# MicroController.net
KiCad netlist of a schematic drawn in Altium Designer
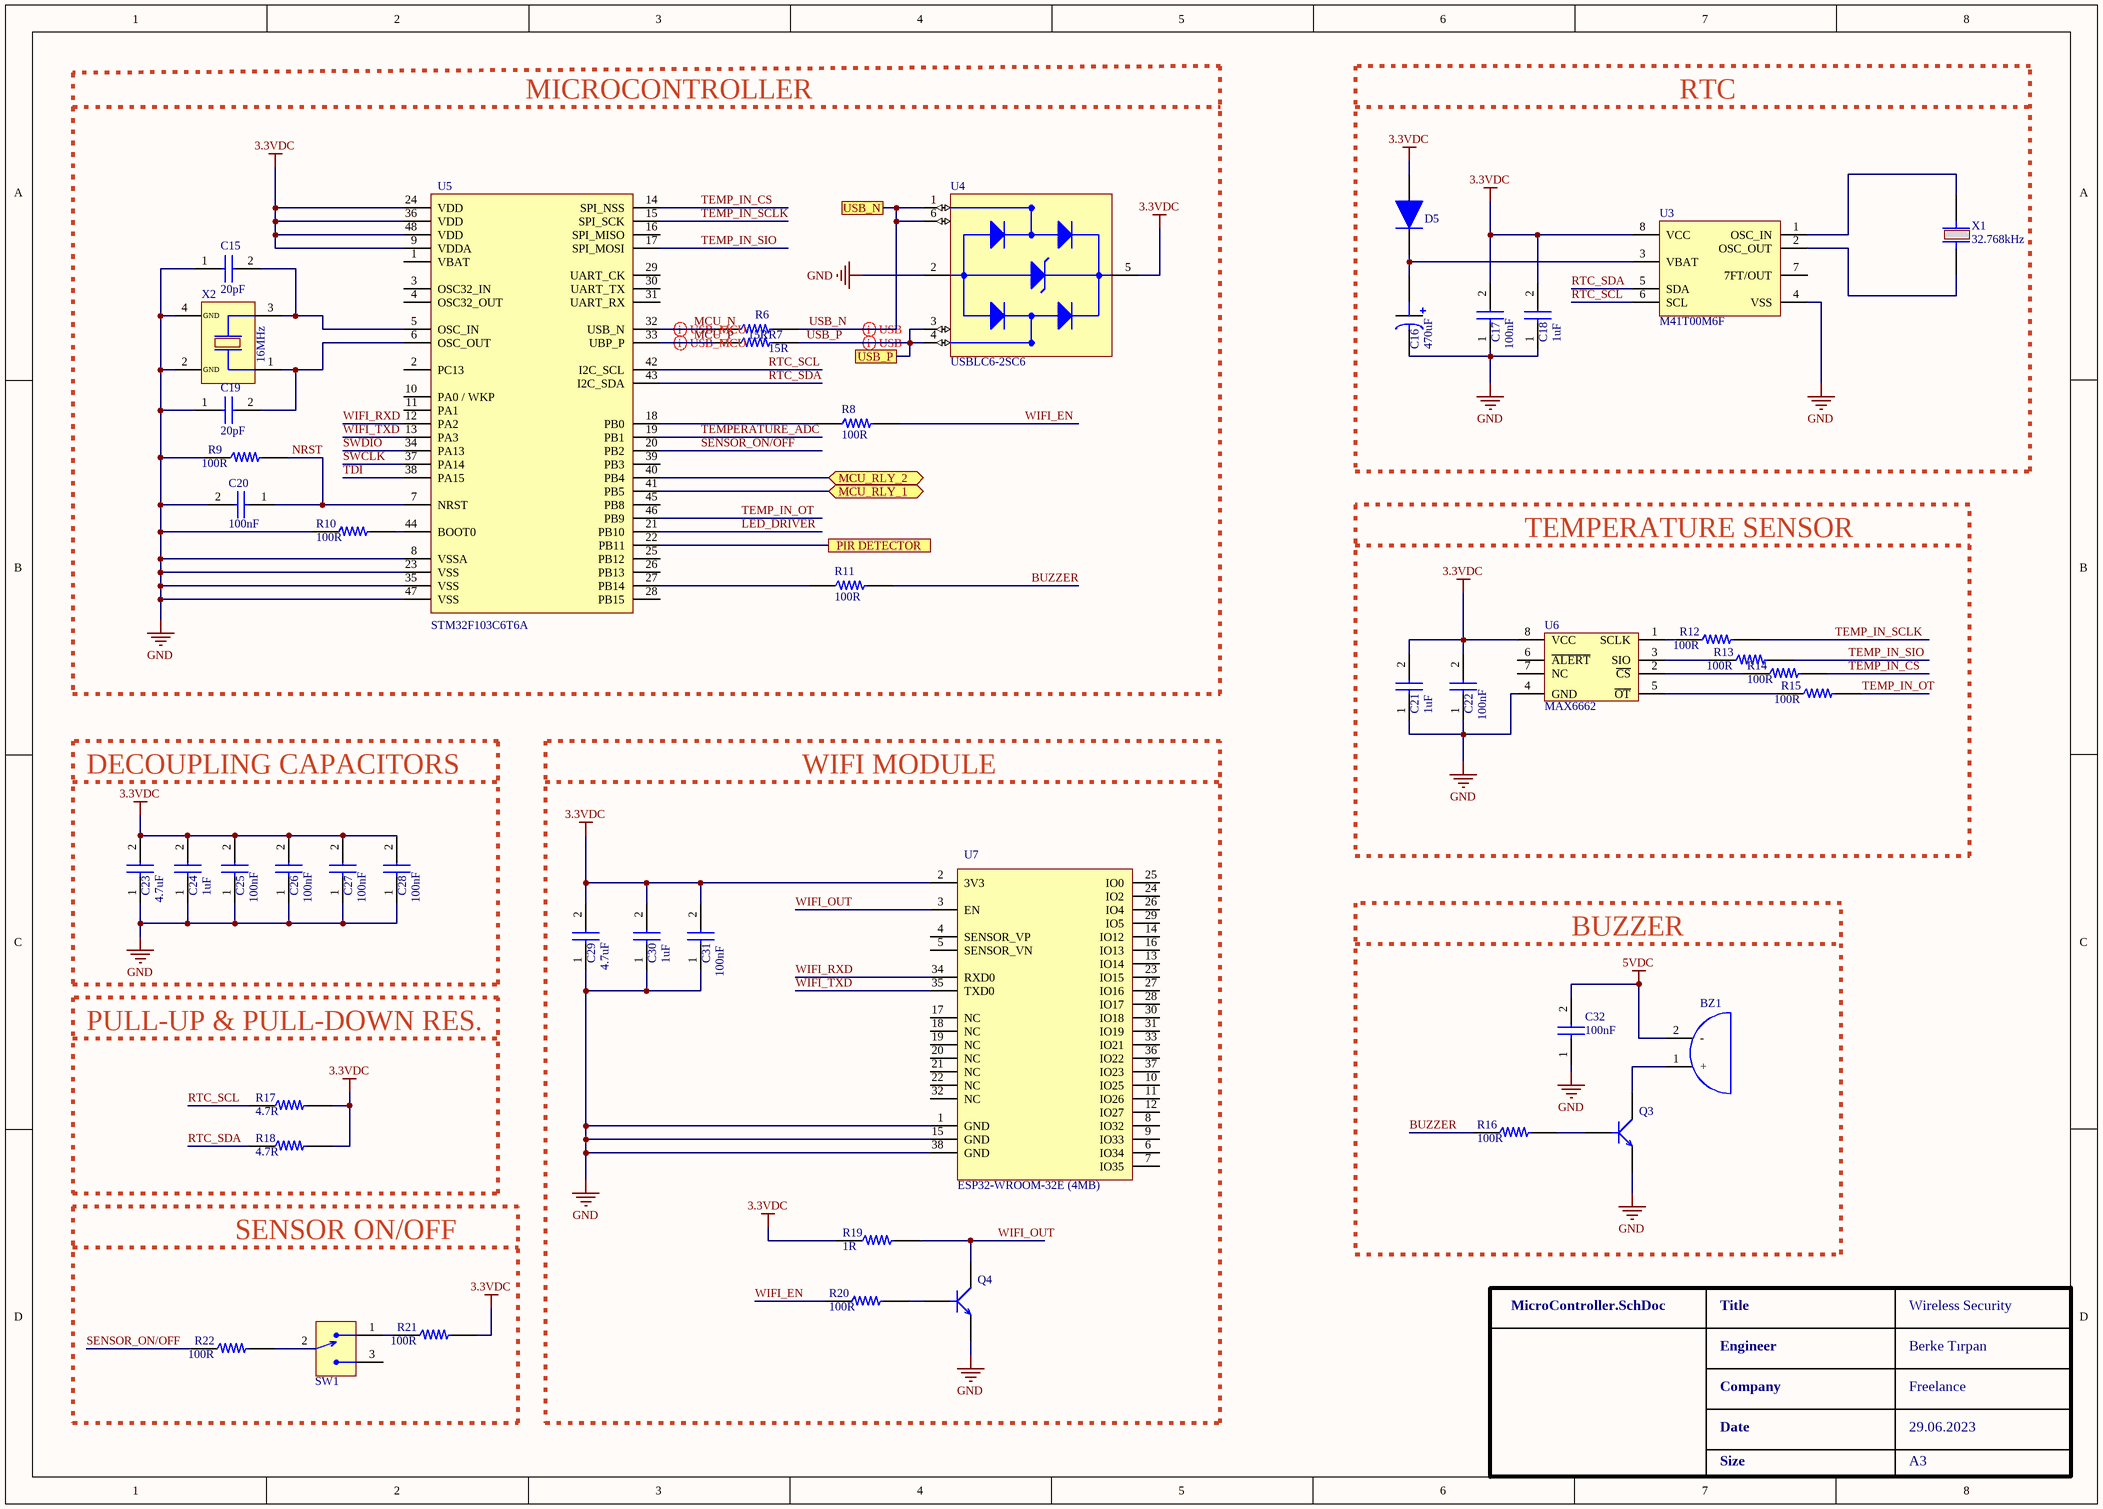
[diagram p0: MicroController.SchDoc]

(export (version "E")
  (design (tool "Eeschema 10.0.6"))
  (components
    (comp (ref "BZ1")
      (value "CMI-9605IC-0580T")
      (footprint "CMI-9605IC-0580T")
      (description "Audio Buzzer Magnetic 3VDC 7VDC 30mA 5VDC 85dB 2600Hz to 2800Hz Through Hole Pin Box")
      (fields (field (name "MANUFACTURER") "CUI Devices"))
      (libsource (lib "Ilk Proje") (part "CMI-9605IC-0580T"))
    )
    (comp (ref "C15")
      (value "CL10C200JB8NNNC")
      (footprint "CAP_0603")
      (description "CAP CER 20PF 50V C0G/NP0 0603")
      (fields
        (field (name "MANUFACTURER") "Samsung")
        (field (name "TOLERANCE") "5%")
        (field (name "CAPACITANCE") "20pF")
      )
      (libsource (lib "Ilk Proje") (part "CAP CER 20pF 0603"))
    )
    (comp (ref "C16")
      (value "ESH477M050AH4AA")
      (footprint "CAP_RADIAL_D10_P5")
      (description "Cap, 470UF, 50V, Alu Elec, Radial")
      (fields
        (field (name "MANUFACTURER") "KEMET")
        (field (name "TOLERANCE") "20%")
        (field (name "CAPACITANCE") "470uF")
      )
      (libsource (lib "Ilk Proje") (part "CAP ALU ELEC 470.UF 50V"))
    )
    (comp (ref "C17")
      (value "CAP CER 100nF 0805")
      (footprint "CAP_0805")
      (description "CAP CER 0.1UF 50V X7R 0805")
      (fields
        (field (name "MANUFACTURER") "Samsung")
        (field (name "MANUFACTURER PART NUMBER") "CL21B104KBCNNNC")
        (field (name "CAPACITANCE") "100nF")
      )
      (libsource (lib "Ilk Proje") (part "CAP CER 100nF 0805"))
    )
    (comp (ref "C18")
      (value "CAP CER 1uF 0805")
      (footprint "CAP_0805")
      (description "CAP CER 1UF 50V X7R %10 0805")
      (fields
        (field (name "MANUFACTURER") "Samsung")
        (field (name "MANUFACTURER PART NUMBER") "CL21B105KBFNNNE")
        (field (name "CAPACITANCE") "1uF")
      )
      (libsource (lib "Ilk Proje") (part "CAP CER 1uF 0805"))
    )
    (comp (ref "C19")
      (value "CL10C200JB8NNNC")
      (footprint "CAP_0603")
      (description "CAP CER 20PF 50V C0G/NP0 0603")
      (fields
        (field (name "MANUFACTURER") "Samsung")
        (field (name "TOLERANCE") "5%")
        (field (name "CAPACITANCE") "20pF")
      )
      (libsource (lib "Ilk Proje") (part "CAP CER 20pF 0603"))
    )
    (comp (ref "C20")
      (value "C0603C104K5RACTU")
      (footprint "CAP_0603")
      (description "Multilayer Ceramic Capacitors (MLCC) - SMD/SMT 50volts 0.1uF X7R 10%")
      (fields
        (field (name "MANUFACTURER") "KEMET")
        (field (name "TOLERANCE") "10%")
        (field (name "CAPACITANCE") "100nF")
      )
      (libsource (lib "Ilk Proje") (part "CAP CER 100nF 0603"))
    )
    (comp (ref "C21")
      (value "CAP CER 1uF 0805")
      (footprint "CAP_0805")
      (description "CAP CER 1UF 50V X7R %10 0805")
      (fields
        (field (name "MANUFACTURER") "Samsung")
        (field (name "MANUFACTURER PART NUMBER") "CL21B105KBFNNNE")
        (field (name "CAPACITANCE") "1uF")
      )
      (libsource (lib "Ilk Proje") (part "CAP CER 1uF 0805"))
    )
    (comp (ref "C22")
      (value "CAP CER 100nF 0805")
      (footprint "CAP_0805")
      (description "CAP CER 0.1UF 50V X7R 0805")
      (fields
        (field (name "MANUFACTURER") "Samsung")
        (field (name "MANUFACTURER PART NUMBER") "CL21B104KBCNNNC")
        (field (name "CAPACITANCE") "100nF")
      )
      (libsource (lib "Ilk Proje") (part "CAP CER 100nF 0805"))
    )
    (comp (ref "C23")
      (value "CAP_CER_4,7UF_0805")
      (footprint "CAP_0805")
      (description "CAP CER 4.7UF 25V %10 0805")
      (fields
        (field (name "MANUFACTURER") "Samsung")
        (field (name "MANUFACTURER PART NUMBER") "CL21A475KAQNNNE")
        (field (name "CAPACITANCE") "4.7uF")
      )
      (libsource (lib "Ilk Proje") (part "CAP_CER_4,7UF_0805"))
    )
    (comp (ref "C24")
      (value "CAP CER 1uF 0805")
      (footprint "CAP_0805")
      (description "CAP CER 1UF 50V X7R %10 0805")
      (fields
        (field (name "MANUFACTURER") "Samsung")
        (field (name "MANUFACTURER PART NUMBER") "CL21B105KBFNNNE")
        (field (name "CAPACITANCE") "1uF")
      )
      (libsource (lib "Ilk Proje") (part "CAP CER 1uF 0805"))
    )
    (comp (ref "C25")
      (value "C0603C104K5RACTU")
      (footprint "CAP_0603")
      (description "Multilayer Ceramic Capacitors (MLCC) - SMD/SMT 50volts 0.1uF X7R 10%")
      (fields
        (field (name "MANUFACTURER") "KEMET")
        (field (name "TOLERANCE") "10%")
        (field (name "CAPACITANCE") "100nF")
      )
      (libsource (lib "Ilk Proje") (part "CAP CER 100nF 0603"))
    )
    (comp (ref "C26")
      (value "C0603C104K5RACTU")
      (footprint "CAP_0603")
      (description "Multilayer Ceramic Capacitors (MLCC) - SMD/SMT 50volts 0.1uF X7R 10%")
      (fields
        (field (name "MANUFACTURER") "KEMET")
        (field (name "TOLERANCE") "10%")
        (field (name "CAPACITANCE") "100nF")
      )
      (libsource (lib "Ilk Proje") (part "CAP CER 100nF 0603"))
    )
    (comp (ref "C27")
      (value "C0603C104K5RACTU")
      (footprint "CAP_0603")
      (description "Multilayer Ceramic Capacitors (MLCC) - SMD/SMT 50volts 0.1uF X7R 10%")
      (fields
        (field (name "MANUFACTURER") "KEMET")
        (field (name "TOLERANCE") "10%")
        (field (name "CAPACITANCE") "100nF")
      )
      (libsource (lib "Ilk Proje") (part "CAP CER 100nF 0603"))
    )
    (comp (ref "C28")
      (value "C0603C104K5RACTU")
      (footprint "CAP_0603")
      (description "Multilayer Ceramic Capacitors (MLCC) - SMD/SMT 50volts 0.1uF X7R 10%")
      (fields
        (field (name "MANUFACTURER") "KEMET")
        (field (name "TOLERANCE") "10%")
        (field (name "CAPACITANCE") "100nF")
      )
      (libsource (lib "Ilk Proje") (part "CAP CER 100nF 0603"))
    )
    (comp (ref "C29")
      (value "CAP_CER_4,7UF_0805")
      (footprint "CAP_0805")
      (description "CAP CER 4.7UF 25V %10 0805")
      (fields
        (field (name "MANUFACTURER") "Samsung")
        (field (name "MANUFACTURER PART NUMBER") "CL21A475KAQNNNE")
        (field (name "CAPACITANCE") "4.7uF")
      )
      (libsource (lib "Ilk Proje") (part "CAP_CER_4,7UF_0805"))
    )
    (comp (ref "C30")
      (value "CAP CER 1uF 0805")
      (footprint "CAP_0805")
      (description "CAP CER 1UF 50V X7R %10 0805")
      (fields
        (field (name "MANUFACTURER") "Samsung")
        (field (name "MANUFACTURER PART NUMBER") "CL21B105KBFNNNE")
        (field (name "CAPACITANCE") "1uF")
      )
      (libsource (lib "Ilk Proje") (part "CAP CER 1uF 0805"))
    )
    (comp (ref "C31")
      (value "CAP CER 100nF 0805")
      (footprint "CAP_0805")
      (description "CAP CER 0.1UF 50V X7R 0805")
      (fields
        (field (name "MANUFACTURER") "Samsung")
        (field (name "MANUFACTURER PART NUMBER") "CL21B104KBCNNNC")
        (field (name "CAPACITANCE") "100nF")
      )
      (libsource (lib "Ilk Proje") (part "CAP CER 100nF 0805"))
    )
    (comp (ref "C32")
      (value "CAP CER 100nF 0805")
      (footprint "CAP_0805")
      (description "CAP CER 0.1UF 50V X7R 0805")
      (fields
        (field (name "MANUFACTURER") "Samsung")
        (field (name "MANUFACTURER PART NUMBER") "CL21B104KBCNNNC")
        (field (name "CAPACITANCE") "100nF")
      )
      (libsource (lib "Ilk Proje") (part "CAP CER 100nF 0805"))
    )
    (comp (ref "D5")
      (value "1N4148WS")
      (footprint "SOD323F")
      (description "VR=75V IF=150mA Trr=4ns P=200mW")
      (fields (field (name "MANUFACTURER") "ON Semiconductor / Fairchild"))
      (libsource (lib "Ilk Proje") (part "1N4148WS"))
    )
    (comp (ref "Q3")
      (value "MMBT3904-7-F")
      (footprint "SOT23-F")
      (description "NPN Ic=200mA Vceo=40V hfe=100~300 fT=310MHz P=300mW SOT-23")
      (fields (field (name "MANUFACTURER") "Diodes Zetex"))
      (libsource (lib "Ilk Proje") (part "MMBT3904-7-F"))
    )
    (comp (ref "Q4")
      (value "MMBT3904-7-F")
      (footprint "SOT23-F")
      (description "NPN Ic=200mA Vceo=40V hfe=100~300 fT=310MHz P=300mW SOT-23")
      (fields (field (name "MANUFACTURER") "Diodes Zetex"))
      (libsource (lib "Ilk Proje") (part "MMBT3904-7-F"))
    )
    (comp (ref "R6")
      (value "RC0603FR-1315KL")
      (footprint "RES_0603")
      (description "Res Thick Film 0603 15K Ohm 1% 0.1W(1/10W) ±100ppm/C Pad SMD T/R")
      (fields
        (field (name "MANUFACTURER") "Yageo")
        (field (name "TOLERANCE") "1%")
        (field (name "RESISTANCE") "15R")
      )
      (libsource (lib "Ilk Proje") (part "RES 15K OHM 0603"))
    )
    (comp (ref "R7")
      (value "RC0603FR-1315KL")
      (footprint "RES_0603")
      (description "Res Thick Film 0603 15K Ohm 1% 0.1W(1/10W) ±100ppm/C Pad SMD T/R")
      (fields
        (field (name "MANUFACTURER") "Yageo")
        (field (name "TOLERANCE") "1%")
        (field (name "RESISTANCE") "15R")
      )
      (libsource (lib "Ilk Proje") (part "RES 15K OHM 0603"))
    )
    (comp (ref "R8")
      (value "RC0603FR-07100KL")
      (footprint "RES_0603")
      (description "RES SMD 100K OHM 1% 1/10W 0603")
      (fields
        (field (name "MANUFACTURER") "Yageo")
        (field (name "TOLERANCE") "1%")
        (field (name "RESISTANCE") "100R")
      )
      (libsource (lib "Ilk Proje") (part "RES 100K OHM 0603"))
    )
    (comp (ref "R9")
      (value "RC0603FR-07100KL")
      (footprint "RES_0603")
      (description "RES SMD 100K OHM 1% 1/10W 0603")
      (fields
        (field (name "MANUFACTURER") "Yageo")
        (field (name "TOLERANCE") "1%")
        (field (name "RESISTANCE") "100R")
      )
      (libsource (lib "Ilk Proje") (part "RES 100K OHM 0603"))
    )
    (comp (ref "R10")
      (value "RC0603FR-07100KL")
      (footprint "RES_0603")
      (description "RES SMD 100K OHM 1% 1/10W 0603")
      (fields
        (field (name "MANUFACTURER") "Yageo")
        (field (name "TOLERANCE") "1%")
        (field (name "RESISTANCE") "100R")
      )
      (libsource (lib "Ilk Proje") (part "RES 100K OHM 0603"))
    )
    (comp (ref "R11")
      (value "RC0603FR-07100KL")
      (footprint "RES_0603")
      (description "RES SMD 100K OHM 1% 1/10W 0603")
      (fields
        (field (name "MANUFACTURER") "Yageo")
        (field (name "TOLERANCE") "1%")
        (field (name "RESISTANCE") "100R")
      )
      (libsource (lib "Ilk Proje") (part "RES 100K OHM 0603"))
    )
    (comp (ref "R12")
      (value "RC0603FR-07100KL")
      (footprint "RES_0603")
      (description "RES SMD 100K OHM 1% 1/10W 0603")
      (fields
        (field (name "MANUFACTURER") "Yageo")
        (field (name "TOLERANCE") "1%")
        (field (name "RESISTANCE") "100R")
      )
      (libsource (lib "Ilk Proje") (part "RES 100K OHM 0603"))
    )
    (comp (ref "R13")
      (value "RC0603FR-07100KL")
      (footprint "RES_0603")
      (description "RES SMD 100K OHM 1% 1/10W 0603")
      (fields
        (field (name "MANUFACTURER") "Yageo")
        (field (name "TOLERANCE") "1%")
        (field (name "RESISTANCE") "100R")
      )
      (libsource (lib "Ilk Proje") (part "RES 100K OHM 0603"))
    )
    (comp (ref "R14")
      (value "RC0603FR-07100KL")
      (footprint "RES_0603")
      (description "RES SMD 100K OHM 1% 1/10W 0603")
      (fields
        (field (name "MANUFACTURER") "Yageo")
        (field (name "TOLERANCE") "1%")
        (field (name "RESISTANCE") "100R")
      )
      (libsource (lib "Ilk Proje") (part "RES 100K OHM 0603"))
    )
    (comp (ref "R15")
      (value "RC0603FR-07100KL")
      (footprint "RES_0603")
      (description "RES SMD 100K OHM 1% 1/10W 0603")
      (fields
        (field (name "MANUFACTURER") "Yageo")
        (field (name "TOLERANCE") "1%")
        (field (name "RESISTANCE") "100R")
      )
      (libsource (lib "Ilk Proje") (part "RES 100K OHM 0603"))
    )
    (comp (ref "R16")
      (value "RC0603FR-07100KL")
      (footprint "RES_0603")
      (description "RES SMD 100K OHM 1% 1/10W 0603")
      (fields
        (field (name "MANUFACTURER") "Yageo")
        (field (name "TOLERANCE") "1%")
        (field (name "RESISTANCE") "100R")
      )
      (libsource (lib "Ilk Proje") (part "RES 100K OHM 0603"))
    )
    (comp (ref "R17")
      (value "RC0603JR-074K7L")
      (footprint "RES_0603")
      (description "Res General Purpose Thick Film 0603 4.7k Ohm 5% 1/10W ±100ppm/°C Molded Paper T/R")
      (fields
        (field (name "MANUFACTURER") "Yageo")
        (field (name "TOLERANCE") "5%")
        (field (name "RESISTANCE") "4.7R")
      )
      (libsource (lib "Ilk Proje") (part "RES 4K7 OHM 0603"))
    )
    (comp (ref "R18")
      (value "RC0603JR-074K7L")
      (footprint "RES_0603")
      (description "Res General Purpose Thick Film 0603 4.7k Ohm 5% 1/10W ±100ppm/°C Molded Paper T/R")
      (fields
        (field (name "MANUFACTURER") "Yageo")
        (field (name "TOLERANCE") "5%")
        (field (name "RESISTANCE") "4.7R")
      )
      (libsource (lib "Ilk Proje") (part "RES 4K7 OHM 0603"))
    )
    (comp (ref "R19")
      (value "RT0603BRD071KL")
      (footprint "RES_0603")
      (description "High Precision-High Stability Chip Resistor Thin Film 0603 1kOhm 0.1% Paper T/R")
      (fields (field (name "MANUFACTURER") "Yageo") (field (name "RESISTANCE") "1R"))
      (libsource (lib "Ilk Proje") (part "RES 1K OHM 0603"))
    )
    (comp (ref "R20")
      (value "RC0603FR-07100KL")
      (footprint "RES_0603")
      (description "RES SMD 100K OHM 1% 1/10W 0603")
      (fields
        (field (name "MANUFACTURER") "Yageo")
        (field (name "TOLERANCE") "1%")
        (field (name "RESISTANCE") "100R")
      )
      (libsource (lib "Ilk Proje") (part "RES 100K OHM 0603"))
    )
    (comp (ref "R21")
      (value "RC0603FR-07100KL")
      (footprint "RES_0603")
      (description "RES SMD 100K OHM 1% 1/10W 0603")
      (fields
        (field (name "MANUFACTURER") "Yageo")
        (field (name "TOLERANCE") "1%")
        (field (name "RESISTANCE") "100R")
      )
      (libsource (lib "Ilk Proje") (part "RES 100K OHM 0603"))
    )
    (comp (ref "R22")
      (value "RC0603FR-07100KL")
      (footprint "RES_0603")
      (description "RES SMD 100K OHM 1% 1/10W 0603")
      (fields
        (field (name "MANUFACTURER") "Yageo")
        (field (name "TOLERANCE") "1%")
        (field (name "RESISTANCE") "100R")
      )
      (libsource (lib "Ilk Proje") (part "RES 100K OHM 0603"))
    )
    (comp (ref "SW1")
      (value "EG1215AA")
      (footprint "EG1215AA")
      (description "Slide Switch, SPDT, 0.025A, 24V, SMD")
      (fields (field (name "MANUFACTURER") "E-Switch"))
      (libsource (lib "Ilk Proje") (part "EG1215AA"))
    )
    (comp (ref "U3")
      (value "M41T00M6F")
      (footprint "SOIC8")
      (description "Real-time Clocks Clock/Calendar I2C, 2-Wire Serial 70uA @ 2V ~ 5.5V SOIC-8_150mil RoHS")
      (fields (field (name "MANUFACTURER") "STMicroelectronics") (field (name "DESIGNED BY") "BERKE"))
      (libsource (lib "Ilk Proje") (part "M41T00"))
    )
    (comp (ref "U4")
      (value "USBLC6-2SC6")
      (footprint "SOT-23-6L")
      (description "TVS DIODE 5.25VWM 17VC SOT23-6")
      (fields (field (name "MANUFACTURER") "STMicroelectronics"))
      (libsource (lib "Ilk Proje") (part "USB PROTECTION"))
    )
    (comp (ref "U5")
      (value "STM32F103C6T6A")
      (footprint "LQFP-48")
      (description "MCU 32-bit STM32F ARM Cortex M3 RISC 32KB Flash 2.5V/3.3V 48-Pin LQFP Tray")
      (fields (field (name "MANUFACTURER") "STMicroelectronics") (field (name "DESIGNED BY") "BERKE"))
      (libsource (lib "Ilk Proje") (part "STM32F103C6T6A"))
    )
    (comp (ref "U6")
      (value "MAX6662")
      (footprint "SOIC8")
      (description "Temp Sensor Digital Serial (3-Wire, SPI) 8-Pin SOIC N Tube")
      (fields (field (name "MANUFACTURER") "Maxim") (field (name "MANUFACTURER PART NUMBER") "MAX6662MSA+"))
      (libsource (lib "Ilk Proje") (part "MAX6662"))
    )
    (comp (ref "U7")
      (value "ESP32-WROOM-32E (4MB)")
      (footprint "ESP32-32E")
      (description "Rx Txrx Mod Wifi Trace Ant SMD")
      (fields
        (field (name "MANUFACTURER") "Espressif Systems")
        (field (name "MANUFACTURER PART NUMBER") "ESP32-WROOM-32E-H4")
      )
      (libsource (lib "Ilk Proje") (part "ESP32-WROOM-32E (4MB)"))
    )
    (comp (ref "X1")
      (value "ABS05-32.768KHZ-T")
      (footprint "ABS05")
      (description "Crystal 0.032768MHz ±20ppm (Tol) 12.5pF Flexural 90000Ohm 2-Pin CSMD T/R")
      (fields
        (field (name "MANUFACTURER") "Abracon")
        (field (name "TOLERANCE") "20ppm")
        (field (name "FREQUENCY") "32.768kHz")
      )
      (libsource (lib "Ilk Proje") (part "CRAYSTAL 32768KHz"))
    )
    (comp (ref "X2")
      (value "ECS-160-20-30B-TR")
      (footprint "ECS")
      (description "Crystal 16MHz ±30ppm (Tol) ±50ppm (Stability) 20pF FUND 50Ohm 4-Pin Mini-SMD T/R")
      (fields
        (field (name "MANUFACTURER") "ECS International")
        (field (name "TOLERANCE") "50ppm")
        (field (name "FREQUENCY") "16MHz")
      )
      (libsource (lib "Ilk Proje") (part "CRYSTAL 16MHz"))
    )
  )
  (nets
    (net (code "1") (name "/BUZZER") (class "Default")
      (node (ref "R11") (pin "2") (pinfunction "2_2") (pintype "passive"))
      (node (ref "R16") (pin "1") (pinfunction "1_1") (pintype "passive"))
    )
    (net (code "2") (name "/LED_DRIVER") (class "Default")
      (node (ref "U5") (pin "21") (pinfunction "PB10_21") (pintype "passive"))
    )
    (net (code "3") (name "/MCU_N") (class "Default")
      (node (ref "R6") (pin "1") (pinfunction "1_1") (pintype "passive"))
      (node (ref "U5") (pin "32") (pinfunction "USB_N_32") (pintype "passive"))
    )
    (net (code "4") (name "/MCU_P") (class "Default")
      (node (ref "R7") (pin "1") (pinfunction "1_1") (pintype "passive"))
      (node (ref "U5") (pin "33") (pinfunction "UBP_P_33") (pintype "passive"))
    )
    (net (code "5") (name "/MCU_RLY_1") (class "Default")
      (node (ref "U5") (pin "41") (pinfunction "PB5_41") (pintype "passive"))
    )
    (net (code "6") (name "/MCU_RLY_2") (class "Default")
      (node (ref "U5") (pin "40") (pinfunction "PB4_40") (pintype "passive"))
    )
    (net (code "7") (name "/NRST") (class "Default")
      (node (ref "C20") (pin "1") (pinfunction "1_1") (pintype "passive"))
      (node (ref "R9") (pin "2") (pinfunction "2_2") (pintype "passive"))
      (node (ref "U5") (pin "7") (pinfunction "NRST_7") (pintype "passive"))
    )
    (net (code "8") (name "/PIR DETECTOR") (class "Default")
      (node (ref "U5") (pin "22") (pinfunction "PB11_22") (pintype "passive"))
    )
    (net (code "9") (name "/RTC_SCL") (class "Default")
      (node (ref "R17") (pin "1") (pinfunction "1_1") (pintype "passive"))
      (node (ref "U3") (pin "6") (pinfunction "SCL_6") (pintype "passive"))
      (node (ref "U5") (pin "42") (pinfunction "_I2C_SCL_42") (pintype "passive"))
    )
    (net (code "10") (name "/RTC_SDA") (class "Default")
      (node (ref "R18") (pin "1") (pinfunction "1_1") (pintype "passive"))
      (node (ref "U3") (pin "5") (pinfunction "SDA_5") (pintype "passive"))
      (node (ref "U5") (pin "43") (pinfunction "_I2C_SDA_43") (pintype "passive"))
    )
    (net (code "11") (name "/SENSOR_ON{slash}OFF") (class "Default")
      (node (ref "R22") (pin "1") (pinfunction "1_1") (pintype "passive"))
      (node (ref "U5") (pin "20") (pinfunction "PB2_20") (pintype "passive"))
    )
    (net (code "12") (name "/SWCLK") (class "Default")
      (node (ref "U5") (pin "37") (pinfunction "PA14_37") (pintype "passive"))
    )
    (net (code "13") (name "/SWDIO") (class "Default")
      (node (ref "U5") (pin "34") (pinfunction "PA13_34") (pintype "passive"))
    )
    (net (code "14") (name "/TDI") (class "Default")
      (node (ref "U5") (pin "38") (pinfunction "PA15_38") (pintype "passive"))
    )
    (net (code "15") (name "/TEMPERATURE_ADC") (class "Default")
      (node (ref "U5") (pin "19") (pinfunction "PB1_19") (pintype "passive"))
    )
    (net (code "16") (name "/TEMP_IN_CS") (class "Default")
      (node (ref "R14") (pin "2") (pinfunction "2_2") (pintype "passive"))
      (node (ref "U5") (pin "14") (pinfunction "SPI_NSS_14") (pintype "passive"))
    )
    (net (code "17") (name "/TEMP_IN_OT") (class "Default")
      (node (ref "R15") (pin "2") (pinfunction "2_2") (pintype "passive"))
      (node (ref "U5") (pin "46") (pinfunction "PB9_46") (pintype "passive"))
    )
    (net (code "18") (name "/TEMP_IN_SCLK") (class "Default")
      (node (ref "R12") (pin "2") (pinfunction "2_2") (pintype "passive"))
      (node (ref "U5") (pin "15") (pinfunction "SPI_SCK_15") (pintype "passive"))
    )
    (net (code "19") (name "/TEMP_IN_SIO") (class "Default")
      (node (ref "R13") (pin "2") (pinfunction "2_2") (pintype "passive"))
      (node (ref "U5") (pin "17") (pinfunction "SPI_MOSI_17") (pintype "passive"))
    )
    (net (code "20") (name "/USB_N") (class "Default")
      (node (ref "R6") (pin "2") (pinfunction "2_2") (pintype "passive"))
      (node (ref "U4") (pin "1") (pinfunction "I/O1_IN_1") (pintype "bidirectional"))
      (node (ref "U4") (pin "6") (pinfunction "I/O1_OUT_6") (pintype "bidirectional"))
    )
    (net (code "21") (name "/USB_P") (class "Default")
      (node (ref "R7") (pin "2") (pinfunction "2_2") (pintype "passive"))
      (node (ref "U4") (pin "3") (pinfunction "I/O2_IN_3") (pintype "bidirectional"))
      (node (ref "U4") (pin "4") (pinfunction "I/O2_OUT_4") (pintype "bidirectional"))
    )
    (net (code "22") (name "/WIFI_EN") (class "Default")
      (node (ref "R20") (pin "1") (pinfunction "1_1") (pintype "passive"))
      (node (ref "R8") (pin "2") (pinfunction "2_2") (pintype "passive"))
    )
    (net (code "23") (name "/WIFI_OUT") (class "Default")
      (node (ref "Q4") (pin "3") (pinfunction "C_3") (pintype "power_in"))
      (node (ref "R19") (pin "2") (pinfunction "2_2") (pintype "passive"))
      (node (ref "U7") (pin "3") (pinfunction "EN_3") (pintype "passive"))
    )
    (net (code "24") (name "/WIFI_RXD") (class "Default")
      (node (ref "U5") (pin "12") (pinfunction "PA2_12") (pintype "passive"))
      (node (ref "U7") (pin "34") (pinfunction "RXD0_34") (pintype "passive"))
    )
    (net (code "25") (name "/WIFI_TXD") (class "Default")
      (node (ref "U5") (pin "13") (pinfunction "PA3_13") (pintype "passive"))
      (node (ref "U7") (pin "35") (pinfunction "TXD0_35") (pintype "passive"))
    )
    (net (code "26") (name "3.3VDC") (class "Default")
      (node (ref "C17") (pin "2") (pinfunction "2_2") (pintype "passive"))
      (node (ref "C18") (pin "2") (pinfunction "2_2") (pintype "passive"))
      (node (ref "C21") (pin "2") (pinfunction "2_2") (pintype "passive"))
      (node (ref "C22") (pin "2") (pinfunction "2_2") (pintype "passive"))
      (node (ref "C23") (pin "2") (pinfunction "2_2") (pintype "passive"))
      (node (ref "C24") (pin "2") (pinfunction "2_2") (pintype "passive"))
      (node (ref "C25") (pin "2") (pinfunction "2_2") (pintype "passive"))
      (node (ref "C26") (pin "2") (pinfunction "2_2") (pintype "passive"))
      (node (ref "C27") (pin "2") (pinfunction "2_2") (pintype "passive"))
      (node (ref "C28") (pin "2") (pinfunction "2_2") (pintype "passive"))
      (node (ref "C29") (pin "2") (pinfunction "2_2") (pintype "passive"))
      (node (ref "C30") (pin "2") (pinfunction "2_2") (pintype "passive"))
      (node (ref "C31") (pin "2") (pinfunction "2_2") (pintype "passive"))
      (node (ref "D5") (pin "2") (pinfunction "2_2") (pintype "power_in"))
      (node (ref "R17") (pin "2") (pinfunction "2_2") (pintype "passive"))
      (node (ref "R18") (pin "2") (pinfunction "2_2") (pintype "passive"))
      (node (ref "R19") (pin "1") (pinfunction "1_1") (pintype "passive"))
      (node (ref "R21") (pin "2") (pinfunction "2_2") (pintype "passive"))
      (node (ref "U3") (pin "8") (pinfunction "VCC_8") (pintype "passive"))
      (node (ref "U4") (pin "5") (pinfunction "VBUS_5") (pintype "power_in"))
      (node (ref "U5") (pin "24") (pinfunction "VDD_24") (pintype "passive"))
      (node (ref "U5") (pin "36") (pinfunction "VDD_36") (pintype "passive"))
      (node (ref "U5") (pin "48") (pinfunction "VDD_48") (pintype "passive"))
      (node (ref "U5") (pin "9") (pinfunction "VDDA_9") (pintype "passive"))
      (node (ref "U6") (pin "8") (pinfunction "VCC_8") (pintype "passive"))
      (node (ref "U7") (pin "2") (pinfunction "3V3_2") (pintype "passive"))
    )
    (net (code "27") (name "5VDC") (class "Default")
      (node (ref "BZ1") (pin "2") (pinfunction "-_2") (pintype "passive"))
      (node (ref "C32") (pin "2") (pinfunction "2_2") (pintype "passive"))
    )
    (net (code "28") (name "GND") (class "Default")
      (node (ref "C15") (pin "1") (pinfunction "1_1") (pintype "power_in"))
      (node (ref "C16") (pin "2") (pinfunction "2_2") (pintype "passive"))
      (node (ref "C17") (pin "1") (pinfunction "1_1") (pintype "passive"))
      (node (ref "C18") (pin "1") (pinfunction "1_1") (pintype "passive"))
      (node (ref "C19") (pin "1") (pinfunction "1_1") (pintype "power_in"))
      (node (ref "C20") (pin "2") (pinfunction "2_2") (pintype "passive"))
      (node (ref "C21") (pin "1") (pinfunction "1_1") (pintype "passive"))
      (node (ref "C22") (pin "1") (pinfunction "1_1") (pintype "passive"))
      (node (ref "C23") (pin "1") (pinfunction "1_1") (pintype "passive"))
      (node (ref "C24") (pin "1") (pinfunction "1_1") (pintype "passive"))
      (node (ref "C25") (pin "1") (pinfunction "1_1") (pintype "passive"))
      (node (ref "C26") (pin "1") (pinfunction "1_1") (pintype "passive"))
      (node (ref "C27") (pin "1") (pinfunction "1_1") (pintype "passive"))
      (node (ref "C28") (pin "1") (pinfunction "1_1") (pintype "passive"))
      (node (ref "C29") (pin "1") (pinfunction "1_1") (pintype "passive"))
      (node (ref "C30") (pin "1") (pinfunction "1_1") (pintype "passive"))
      (node (ref "C31") (pin "1") (pinfunction "1_1") (pintype "passive"))
      (node (ref "C32") (pin "1") (pinfunction "1_1") (pintype "passive"))
      (node (ref "Q3") (pin "2") (pinfunction "E_2") (pintype "power_in"))
      (node (ref "Q4") (pin "2") (pinfunction "E_2") (pintype "power_in"))
      (node (ref "R10") (pin "1") (pinfunction "1_1") (pintype "passive"))
      (node (ref "R9") (pin "1") (pinfunction "1_1") (pintype "passive"))
      (node (ref "U3") (pin "4") (pinfunction "VSS_4") (pintype "passive"))
      (node (ref "U4") (pin "2") (pinfunction "GND_2") (pintype "power_in"))
      (node (ref "U5") (pin "23") (pinfunction "VSS_23") (pintype "passive"))
      (node (ref "U5") (pin "35") (pinfunction "VSS_35") (pintype "passive"))
      (node (ref "U5") (pin "47") (pinfunction "VSS_47") (pintype "passive"))
      (node (ref "U5") (pin "8") (pinfunction "VSSA_8") (pintype "passive"))
      (node (ref "U6") (pin "4") (pinfunction "GND_4") (pintype "passive"))
      (node (ref "U7") (pin "1") (pinfunction "GND_1") (pintype "passive"))
      (node (ref "U7") (pin "15") (pinfunction "GND_15") (pintype "passive"))
      (node (ref "U7") (pin "38") (pinfunction "GND_38") (pintype "passive"))
      (node (ref "X2") (pin "2") (pinfunction "GND_2") (pintype "power_in"))
      (node (ref "X2") (pin "4") (pinfunction "GND_4") (pintype "power_in"))
    )
    (net (code "29") (name "Net-(BZ1-+)") (class "Default")
      (node (ref "BZ1") (pin "1") (pinfunction "+_1") (pintype "passive"))
      (node (ref "Q3") (pin "3") (pinfunction "C_3") (pintype "power_in"))
    )
    (net (code "30") (name "Net-(Q3-B)") (class "Default")
      (node (ref "Q3") (pin "1") (pinfunction "B_1") (pintype "power_in"))
      (node (ref "R16") (pin "2") (pinfunction "2_2") (pintype "passive"))
    )
    (net (code "31") (name "Net-(Q4-B)") (class "Default")
      (node (ref "Q4") (pin "1") (pinfunction "B_1") (pintype "power_in"))
      (node (ref "R20") (pin "2") (pinfunction "2_2") (pintype "passive"))
    )
    (net (code "32") (name "Net-(R21-Pad1)") (class "Default")
      (node (ref "R21") (pin "1") (pinfunction "1_1") (pintype "passive"))
      (node (ref "SW1") (pin "1") (pinfunction "1_1") (pintype "passive"))
    )
    (net (code "33") (name "Net-(R22-Pad2)") (class "Default")
      (node (ref "R22") (pin "2") (pinfunction "2_2") (pintype "passive"))
      (node (ref "SW1") (pin "2") (pinfunction "2_2") (pintype "passive"))
    )
    (net (code "34") (name "Net-(U3-OSC_IN)") (class "Default")
      (node (ref "U3") (pin "1") (pinfunction "OSC_IN_1") (pintype "passive"))
      (node (ref "X1") (pin "2") (pintype "passive"))
    )
    (net (code "35") (name "Net-(U3-OSC_OUT)") (class "Default")
      (node (ref "U3") (pin "2") (pinfunction "OSC_OUT_2") (pintype "passive"))
      (node (ref "X1") (pin "1") (pintype "passive"))
    )
    (net (code "36") (name "Net-(U3-VBAT)") (class "Default")
      (node (ref "C16") (pin "1") (pinfunction "1_1") (pintype "passive"))
      (node (ref "D5") (pin "1") (pinfunction "1_1") (pintype "power_in"))
      (node (ref "U3") (pin "3") (pinfunction "VBAT_3") (pintype "passive"))
    )
    (net (code "37") (name "Net-(U5-BOOT0)") (class "Default")
      (node (ref "R10") (pin "2") (pinfunction "2_2") (pintype "passive"))
      (node (ref "U5") (pin "44") (pinfunction "BOOT0_44") (pintype "passive"))
    )
    (net (code "38") (name "Net-(U5-OSC_IN)") (class "Default")
      (node (ref "C15") (pin "2") (pinfunction "2_2") (pintype "passive"))
      (node (ref "U5") (pin "5") (pinfunction "OSC_IN_5") (pintype "passive"))
      (node (ref "X2") (pin "3") (pinfunction "3_3") (pintype "passive"))
    )
    (net (code "39") (name "Net-(U5-OSC_OUT)") (class "Default")
      (node (ref "C19") (pin "2") (pinfunction "2_2") (pintype "passive"))
      (node (ref "U5") (pin "6") (pinfunction "OSC_OUT_6") (pintype "passive"))
      (node (ref "X2") (pin "1") (pintype "passive"))
    )
    (net (code "40") (name "Net-(U5-PB0)") (class "Default")
      (node (ref "R8") (pin "1") (pinfunction "1_1") (pintype "passive"))
      (node (ref "U5") (pin "18") (pinfunction "PB0_18") (pintype "passive"))
    )
    (net (code "41") (name "Net-(U5-PB14)") (class "Default")
      (node (ref "R11") (pin "1") (pinfunction "1_1") (pintype "passive"))
      (node (ref "U5") (pin "27") (pinfunction "PB14_27") (pintype "passive"))
    )
    (net (code "42") (name "Net-(U6-SCLK)") (class "Default")
      (node (ref "R12") (pin "1") (pinfunction "1_1") (pintype "passive"))
      (node (ref "U6") (pin "1") (pinfunction "SCLK_1") (pintype "passive"))
    )
    (net (code "43") (name "Net-(U6-SIO)") (class "Default")
      (node (ref "R13") (pin "1") (pinfunction "1_1") (pintype "passive"))
      (node (ref "U6") (pin "3") (pinfunction "SIO_3") (pintype "passive"))
    )
    (net (code "44") (name "Net-(U6-~{CS})") (class "Default")
      (node (ref "R14") (pin "1") (pinfunction "1_1") (pintype "passive"))
      (node (ref "U6") (pin "2") (pinfunction "~{CS}_2") (pintype "passive"))
    )
    (net (code "45") (name "Net-(U6-~{OT})") (class "Default")
      (node (ref "R15") (pin "1") (pinfunction "1_1") (pintype "passive"))
      (node (ref "U6") (pin "5") (pinfunction "~{OT}_5") (pintype "passive"))
    )
    (net (code "46") (name "unconnected-(SW1-Pad3)") (class "Default")
      (node (ref "SW1") (pin "3") (pinfunction "3_3") (pintype "passive"))
    )
    (net (code "47") (name "unconnected-(U3-7FT{slash}OUT-Pad7)") (class "Default")
      (node (ref "U3") (pin "7") (pinfunction "7FT/OUT_7") (pintype "passive"))
    )
    (net (code "48") (name "unconnected-(U5-OSC32_IN-Pad3)") (class "Default")
      (node (ref "U5") (pin "3") (pinfunction "OSC32_IN_3") (pintype "passive"))
    )
    (net (code "49") (name "unconnected-(U5-OSC32_OUT-Pad4)") (class "Default")
      (node (ref "U5") (pin "4") (pinfunction "OSC32_OUT_4") (pintype "passive"))
    )
    (net (code "50") (name "unconnected-(U5-PA0_{slash}_WKP-Pad10)") (class "Default")
      (node (ref "U5") (pin "10") (pinfunction "PA0_/_WKP_10") (pintype "passive"))
    )
    (net (code "51") (name "unconnected-(U5-PA1-Pad11)") (class "Default")
      (node (ref "U5") (pin "11") (pinfunction "PA1_11") (pintype "passive"))
    )
    (net (code "52") (name "unconnected-(U5-PB3-Pad39)") (class "Default")
      (node (ref "U5") (pin "39") (pinfunction "PB3_39") (pintype "passive"))
    )
    (net (code "53") (name "unconnected-(U5-PB8-Pad45)") (class "Default")
      (node (ref "U5") (pin "45") (pinfunction "PB8_45") (pintype "passive"))
    )
    (net (code "54") (name "unconnected-(U5-PB12-Pad25)") (class "Default")
      (node (ref "U5") (pin "25") (pinfunction "PB12_25") (pintype "passive"))
    )
    (net (code "55") (name "unconnected-(U5-PB13-Pad26)") (class "Default")
      (node (ref "U5") (pin "26") (pinfunction "PB13_26") (pintype "passive"))
    )
    (net (code "56") (name "unconnected-(U5-PB15-Pad28)") (class "Default")
      (node (ref "U5") (pin "28") (pinfunction "PB15_28") (pintype "passive"))
    )
    (net (code "57") (name "unconnected-(U5-PC13-Pad2)") (class "Default")
      (node (ref "U5") (pin "2") (pinfunction "PC13_2") (pintype "passive"))
    )
    (net (code "58") (name "unconnected-(U5-SPI_MISO-Pad16)") (class "Default")
      (node (ref "U5") (pin "16") (pinfunction "SPI_MISO_16") (pintype "passive"))
    )
    (net (code "59") (name "unconnected-(U5-UART_CK-Pad29)") (class "Default")
      (node (ref "U5") (pin "29") (pinfunction "UART_CK_29") (pintype "passive"))
    )
    (net (code "60") (name "unconnected-(U5-UART_RX-Pad31)") (class "Default")
      (node (ref "U5") (pin "31") (pinfunction "UART_RX_31") (pintype "passive"))
    )
    (net (code "61") (name "unconnected-(U5-UART_TX-Pad30)") (class "Default")
      (node (ref "U5") (pin "30") (pinfunction "UART_TX_30") (pintype "passive"))
    )
    (net (code "62") (name "unconnected-(U5-VBAT-Pad1)") (class "Default")
      (node (ref "U5") (pin "1") (pinfunction "VBAT_1") (pintype "passive"))
    )
    (net (code "63") (name "unconnected-(U6-NC-Pad7)") (class "Default")
      (node (ref "U6") (pin "7") (pinfunction "NC_7") (pintype "passive"))
    )
    (net (code "64") (name "unconnected-(U6-~{ALERT}-Pad6)") (class "Default")
      (node (ref "U6") (pin "6") (pinfunction "~{ALERT}_6") (pintype "passive"))
    )
    (net (code "65") (name "unconnected-(U7-IO0-Pad25)") (class "Default")
      (node (ref "U7") (pin "25") (pinfunction "IO0_25") (pintype "passive"))
    )
    (net (code "66") (name "unconnected-(U7-IO2-Pad24)") (class "Default")
      (node (ref "U7") (pin "24") (pinfunction "IO2_24") (pintype "passive"))
    )
    (net (code "67") (name "unconnected-(U7-IO4-Pad26)") (class "Default")
      (node (ref "U7") (pin "26") (pinfunction "IO4_26") (pintype "passive"))
    )
    (net (code "68") (name "unconnected-(U7-IO5-Pad29)") (class "Default")
      (node (ref "U7") (pin "29") (pinfunction "IO5_29") (pintype "passive"))
    )
    (net (code "69") (name "unconnected-(U7-IO12-Pad14)") (class "Default")
      (node (ref "U7") (pin "14") (pinfunction "IO12_14") (pintype "passive"))
    )
    (net (code "70") (name "unconnected-(U7-IO13-Pad16)") (class "Default")
      (node (ref "U7") (pin "16") (pinfunction "IO13_16") (pintype "passive"))
    )
    (net (code "71") (name "unconnected-(U7-IO14-Pad13)") (class "Default")
      (node (ref "U7") (pin "13") (pinfunction "IO14_13") (pintype "passive"))
    )
    (net (code "72") (name "unconnected-(U7-IO15-Pad23)") (class "Default")
      (node (ref "U7") (pin "23") (pinfunction "IO15_23") (pintype "passive"))
    )
    (net (code "73") (name "unconnected-(U7-IO16-Pad27)") (class "Default")
      (node (ref "U7") (pin "27") (pinfunction "IO16_27") (pintype "passive"))
    )
    (net (code "74") (name "unconnected-(U7-IO17-Pad28)") (class "Default")
      (node (ref "U7") (pin "28") (pinfunction "IO17_28") (pintype "passive"))
    )
    (net (code "75") (name "unconnected-(U7-IO18-Pad30)") (class "Default")
      (node (ref "U7") (pin "30") (pinfunction "IO18_30") (pintype "passive"))
    )
    (net (code "76") (name "unconnected-(U7-IO19-Pad31)") (class "Default")
      (node (ref "U7") (pin "31") (pinfunction "IO19_31") (pintype "passive"))
    )
    (net (code "77") (name "unconnected-(U7-IO21-Pad33)") (class "Default")
      (node (ref "U7") (pin "33") (pinfunction "IO21_33") (pintype "passive"))
    )
    (net (code "78") (name "unconnected-(U7-IO22-Pad36)") (class "Default")
      (node (ref "U7") (pin "36") (pinfunction "IO22_36") (pintype "passive"))
    )
    (net (code "79") (name "unconnected-(U7-IO23-Pad37)") (class "Default")
      (node (ref "U7") (pin "37") (pinfunction "IO23_37") (pintype "passive"))
    )
    (net (code "80") (name "unconnected-(U7-IO25-Pad10)") (class "Default")
      (node (ref "U7") (pin "10") (pinfunction "IO25_10") (pintype "passive"))
    )
    (net (code "81") (name "unconnected-(U7-IO26-Pad11)") (class "Default")
      (node (ref "U7") (pin "11") (pinfunction "IO26_11") (pintype "passive"))
    )
    (net (code "82") (name "unconnected-(U7-IO27-Pad12)") (class "Default")
      (node (ref "U7") (pin "12") (pinfunction "IO27_12") (pintype "passive"))
    )
    (net (code "83") (name "unconnected-(U7-IO32-Pad8)") (class "Default")
      (node (ref "U7") (pin "8") (pinfunction "IO32_8") (pintype "passive"))
    )
    (net (code "84") (name "unconnected-(U7-IO33-Pad9)") (class "Default")
      (node (ref "U7") (pin "9") (pinfunction "IO33_9") (pintype "passive"))
    )
    (net (code "85") (name "unconnected-(U7-IO34-Pad6)") (class "Default")
      (node (ref "U7") (pin "6") (pinfunction "IO34_6") (pintype "passive"))
    )
    (net (code "86") (name "unconnected-(U7-IO35-Pad7)") (class "Default")
      (node (ref "U7") (pin "7") (pinfunction "IO35_7") (pintype "passive"))
    )
    (net (code "87") (name "unconnected-(U7-NC-Pad17)") (class "Default")
      (node (ref "U7") (pin "17") (pinfunction "NC_17") (pintype "passive"))
    )
    (net (code "88") (name "unconnected-(U7-NC-Pad18)") (class "Default")
      (node (ref "U7") (pin "18") (pinfunction "NC_18") (pintype "passive"))
    )
    (net (code "89") (name "unconnected-(U7-NC-Pad19)") (class "Default")
      (node (ref "U7") (pin "19") (pinfunction "NC_19") (pintype "passive"))
    )
    (net (code "90") (name "unconnected-(U7-NC-Pad20)") (class "Default")
      (node (ref "U7") (pin "20") (pinfunction "NC_20") (pintype "passive"))
    )
    (net (code "91") (name "unconnected-(U7-NC-Pad21)") (class "Default")
      (node (ref "U7") (pin "21") (pinfunction "NC_21") (pintype "passive"))
    )
    (net (code "92") (name "unconnected-(U7-NC-Pad22)") (class "Default")
      (node (ref "U7") (pin "22") (pinfunction "NC_22") (pintype "passive"))
    )
    (net (code "93") (name "unconnected-(U7-NC-Pad32)") (class "Default")
      (node (ref "U7") (pin "32") (pinfunction "NC_32") (pintype "passive"))
    )
    (net (code "94") (name "unconnected-(U7-SENSOR_VN-Pad5)") (class "Default")
      (node (ref "U7") (pin "5") (pinfunction "SENSOR_VN_5") (pintype "passive"))
    )
    (net (code "95") (name "unconnected-(U7-SENSOR_VP-Pad4)") (class "Default")
      (node (ref "U7") (pin "4") (pinfunction "SENSOR_VP_4") (pintype "passive"))
    )
  )
)
